# GCtoUSBv1_1.net
KiCad netlist of a schematic drawn in EAGLE
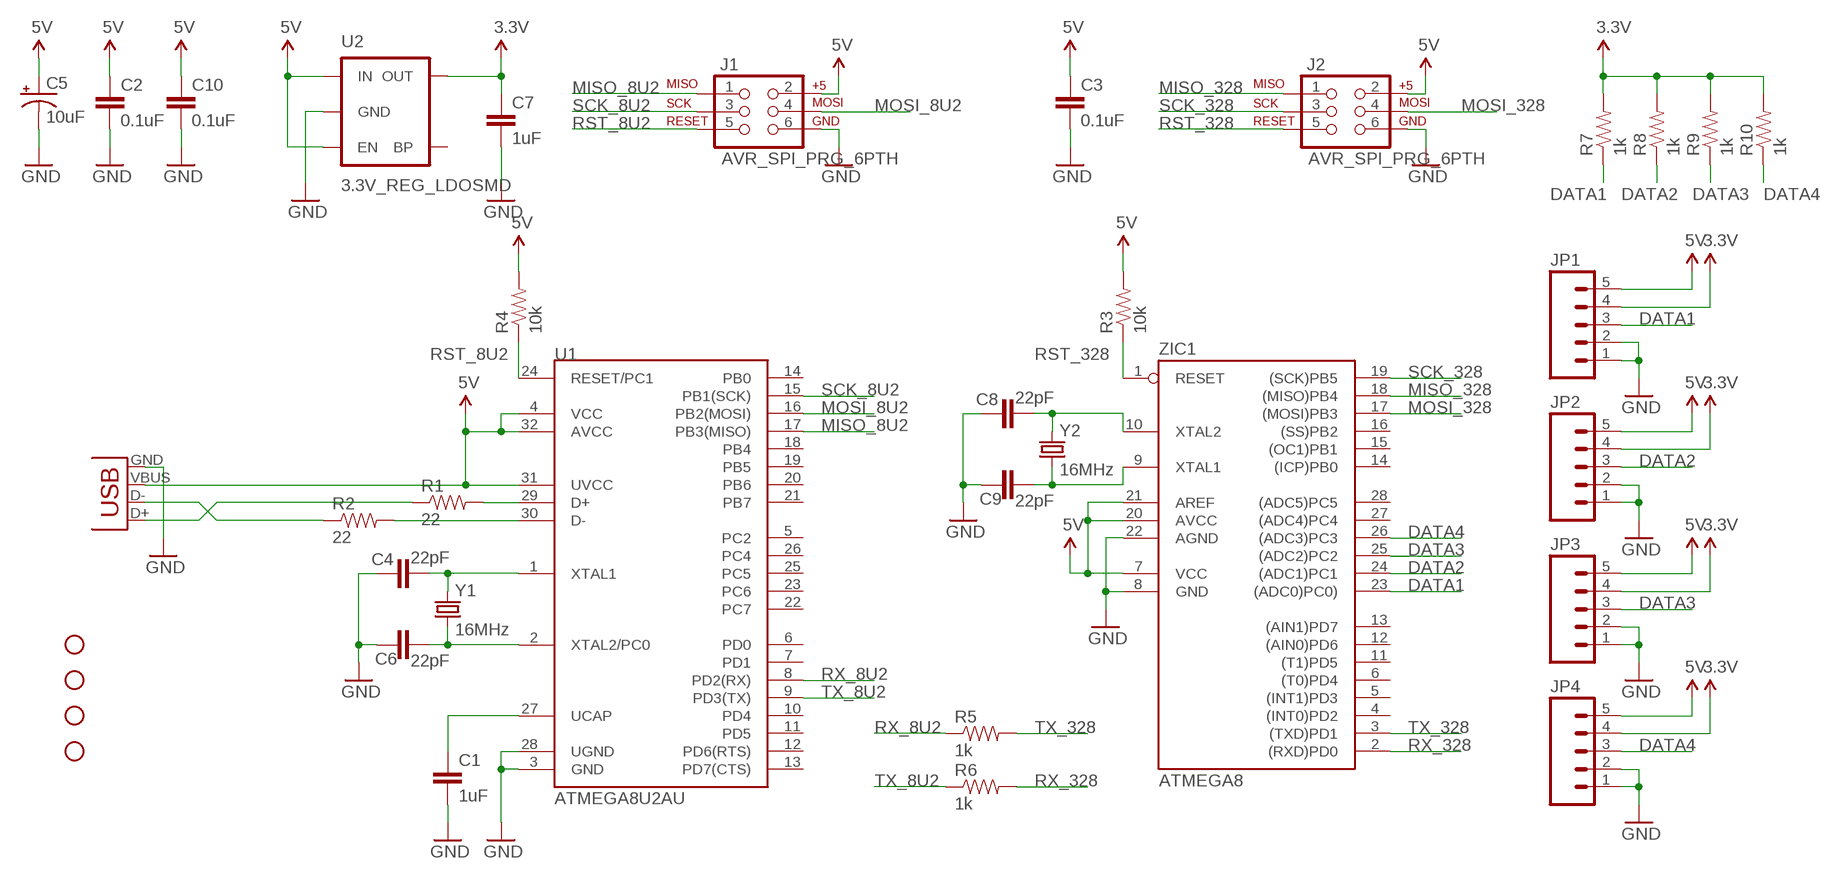
[diagram p0: schematic, sheet 1]

(export (version "E")
  (design (tool "Eeschema 10.0.6"))
  (components
    (comp (ref "C1")
      (value "1uF")
      (footprint "eagle-import:CAP-PTH-5MM")
      (libsource (lib "eagle-import") (part "CAPPTH1"))
    )
    (comp (ref "C2")
      (value "0.1uF")
      (footprint "eagle-import:CAP-PTH-SMALL")
      (libsource (lib "eagle-import") (part "CAPPTH"))
    )
    (comp (ref "C3")
      (value "0.1uF")
      (footprint "eagle-import:CAP-PTH-SMALL")
      (libsource (lib "eagle-import") (part "CAPPTH"))
    )
    (comp (ref "C4")
      (value "22pF")
      (footprint "eagle-import:CAP-PTH-SMALL")
      (libsource (lib "eagle-import") (part "CAPPTH"))
    )
    (comp (ref "C5")
      (value "10uF")
      (footprint "eagle-import:CPOL-RADIAL-10UF-25V")
      (libsource (lib "eagle-import") (part "CAP_POLPTH2"))
    )
    (comp (ref "C6")
      (value "22pF")
      (footprint "eagle-import:CAP-PTH-SMALL")
      (libsource (lib "eagle-import") (part "CAPPTH"))
    )
    (comp (ref "C7")
      (value "1uF")
      (footprint "eagle-import:CAP-PTH-5MM")
      (libsource (lib "eagle-import") (part "CAPPTH1"))
    )
    (comp (ref "C8")
      (value "22pF")
      (footprint "eagle-import:CAP-PTH-SMALL")
      (libsource (lib "eagle-import") (part "CAPPTH"))
    )
    (comp (ref "C9")
      (value "22pF")
      (footprint "eagle-import:CAP-PTH-SMALL")
      (libsource (lib "eagle-import") (part "CAPPTH"))
    )
    (comp (ref "C10")
      (value "0.1uF")
      (footprint "eagle-import:CAP-PTH-SMALL")
      (libsource (lib "eagle-import") (part "CAPPTH"))
    )
    (comp (ref "J1")
      (value "AVR_SPI_PRG_6PTH")
      (footprint "eagle-import:2X3")
      (libsource (lib "eagle-import") (part "AVR_SPI_PRG_6PTH"))
    )
    (comp (ref "J2")
      (value "AVR_SPI_PRG_6PTH")
      (footprint "eagle-import:2X3")
      (libsource (lib "eagle-import") (part "AVR_SPI_PRG_6PTH"))
    )
    (comp (ref "JP1")
      (value "M05PTH")
      (footprint "eagle-import:1X05")
      (libsource (lib "eagle-import") (part "M05PTH"))
    )
    (comp (ref "JP2")
      (value "M05PTH")
      (footprint "eagle-import:1X05")
      (libsource (lib "eagle-import") (part "M05PTH"))
    )
    (comp (ref "JP3")
      (value "M05PTH")
      (footprint "eagle-import:1X05")
      (libsource (lib "eagle-import") (part "M05PTH"))
    )
    (comp (ref "JP4")
      (value "M05PTH")
      (footprint "eagle-import:1X05")
      (libsource (lib "eagle-import") (part "M05PTH"))
    )
    (comp (ref "JP5")
      (value "STAND-OFF")
      (footprint "eagle-import:STAND-OFF")
      (libsource (lib "eagle-import") (part "STAND-OFF"))
    )
    (comp (ref "JP6")
      (value "STAND-OFF")
      (footprint "eagle-import:STAND-OFF")
      (libsource (lib "eagle-import") (part "STAND-OFF"))
    )
    (comp (ref "JP7")
      (value "STAND-OFF")
      (footprint "eagle-import:STAND-OFF")
      (libsource (lib "eagle-import") (part "STAND-OFF"))
    )
    (comp (ref "JP8")
      (value "STAND-OFF")
      (footprint "eagle-import:STAND-OFF")
      (libsource (lib "eagle-import") (part "STAND-OFF"))
    )
    (comp (ref "R1")
      (value "22")
      (footprint "eagle-import:AXIAL-0.4")
      (libsource (lib "eagle-import") (part "RESISTORPTH-1/4W"))
    )
    (comp (ref "R2")
      (value "22")
      (footprint "eagle-import:AXIAL-0.4")
      (libsource (lib "eagle-import") (part "RESISTORPTH-1/4W"))
    )
    (comp (ref "R3")
      (value "10k")
      (footprint "eagle-import:AXIAL-0.5")
      (libsource (lib "eagle-import") (part "RESISTORPTH-1/2W"))
    )
    (comp (ref "R4")
      (value "10k")
      (footprint "eagle-import:AXIAL-0.5")
      (libsource (lib "eagle-import") (part "RESISTORPTH-1/2W"))
    )
    (comp (ref "R5")
      (value "1k")
      (footprint "eagle-import:AXIAL-0.5")
      (libsource (lib "eagle-import") (part "RESISTORPTH-1/2W"))
    )
    (comp (ref "R6")
      (value "1k")
      (footprint "eagle-import:AXIAL-0.5")
      (libsource (lib "eagle-import") (part "RESISTORPTH-1/2W"))
    )
    (comp (ref "R7")
      (value "1k")
      (footprint "eagle-import:AXIAL-0.5")
      (libsource (lib "eagle-import") (part "RESISTORPTH-1/2W"))
    )
    (comp (ref "R8")
      (value "1k")
      (footprint "eagle-import:AXIAL-0.5")
      (libsource (lib "eagle-import") (part "RESISTORPTH-1/2W"))
    )
    (comp (ref "R9")
      (value "1k")
      (footprint "eagle-import:AXIAL-0.5")
      (libsource (lib "eagle-import") (part "RESISTORPTH-1/2W"))
    )
    (comp (ref "R10")
      (value "1k")
      (footprint "eagle-import:AXIAL-0.5")
      (libsource (lib "eagle-import") (part "RESISTORPTH-1/2W"))
    )
    (comp (ref "U1")
      (value "ATMEGA8U2AU")
      (footprint "eagle-import:TQFP32-08")
      (libsource (lib "eagle-import") (part "ATMEGA8U2AU"))
    )
    (comp (ref "U2")
      (value "3.3V_REG_LDOSMD")
      (footprint "eagle-import:SOT23-5")
      (libsource (lib "eagle-import") (part "V_REG_LDOSMD"))
    )
    (comp (ref "X1")
      (value "USBSMD")
      (footprint "eagle-import:USB-MINIB")
      (libsource (lib "eagle-import") (part "USBSMD"))
    )
    (comp (ref "Y1")
      (value "16MHz")
      (footprint "eagle-import:HC49US")
      (libsource (lib "eagle-import") (part "CRYSTALHC49US"))
    )
    (comp (ref "Y2")
      (value "16MHz")
      (footprint "eagle-import:HC49US")
      (libsource (lib "eagle-import") (part "CRYSTALHC49US"))
    )
    (comp (ref "ZIC1")
      (value "ATMEGA8")
      (footprint "eagle-import:DIL28-3")
      (libsource (lib "eagle-import") (part "AT90S4433P"))
    )
  )
  (nets
    (net (code "1") (name "/DATA1") (class "Default")
      (node (ref "JP1") (pin "3") (pinfunction "3_3") (pintype "passive"))
      (node (ref "R7") (pin "P$1") (pinfunction "1_P$1") (pintype "passive"))
      (node (ref "ZIC1") (pin "23") (pinfunction "(ADC0)PC0)_23") (pintype "bidirectional"))
    )
    (net (code "2") (name "/DATA2") (class "Default")
      (node (ref "JP2") (pin "3") (pinfunction "3_3") (pintype "passive"))
      (node (ref "R8") (pin "P$1") (pinfunction "1_P$1") (pintype "passive"))
      (node (ref "ZIC1") (pin "24") (pinfunction "(ADC1)PC1_24") (pintype "bidirectional"))
    )
    (net (code "3") (name "/DATA3") (class "Default")
      (node (ref "JP3") (pin "3") (pinfunction "3_3") (pintype "passive"))
      (node (ref "R9") (pin "P$1") (pinfunction "1_P$1") (pintype "passive"))
      (node (ref "ZIC1") (pin "25") (pinfunction "(ADC2)PC2_25") (pintype "bidirectional"))
    )
    (net (code "4") (name "/DATA4") (class "Default")
      (node (ref "JP4") (pin "3") (pinfunction "3_3") (pintype "passive"))
      (node (ref "R10") (pin "P$1") (pinfunction "1_P$1") (pintype "passive"))
      (node (ref "ZIC1") (pin "26") (pinfunction "(ADC3)PC3_26") (pintype "bidirectional"))
    )
    (net (code "5") (name "/MISO_8U2") (class "Default")
      (node (ref "J1") (pin "1") (pinfunction "1_1") (pintype "passive"))
      (node (ref "U1") (pin "17") (pinfunction "PB3(MISO)_17") (pintype "bidirectional"))
    )
    (net (code "6") (name "/MISO_328") (class "Default")
      (node (ref "J2") (pin "1") (pinfunction "1_1") (pintype "passive"))
      (node (ref "ZIC1") (pin "18") (pinfunction "(MISO)PB4_18") (pintype "bidirectional"))
    )
    (net (code "7") (name "/MOSI_8U2") (class "Default")
      (node (ref "J1") (pin "4") (pinfunction "4_4") (pintype "passive"))
      (node (ref "U1") (pin "16") (pinfunction "PB2(MOSI)_16") (pintype "bidirectional"))
    )
    (net (code "8") (name "/MOSI_328") (class "Default")
      (node (ref "J2") (pin "4") (pinfunction "4_4") (pintype "passive"))
      (node (ref "ZIC1") (pin "17") (pinfunction "(MOSI)PB3_17") (pintype "bidirectional"))
    )
    (net (code "9") (name "/RST_8U2") (class "Default")
      (node (ref "J1") (pin "5") (pinfunction "5_5") (pintype "passive"))
      (node (ref "R4") (pin "P$1") (pinfunction "1_P$1") (pintype "passive"))
      (node (ref "U1") (pin "24") (pinfunction "RESET/PC1_24") (pintype "bidirectional"))
    )
    (net (code "10") (name "/RST_328") (class "Default")
      (node (ref "J2") (pin "5") (pinfunction "5_5") (pintype "passive"))
      (node (ref "R3") (pin "P$1") (pinfunction "1_P$1") (pintype "passive"))
      (node (ref "ZIC1") (pin "1") (pinfunction "RESET_1") (pintype "input"))
    )
    (net (code "11") (name "/RX_8U2") (class "Default")
      (node (ref "R5") (pin "P$1") (pinfunction "1_P$1") (pintype "passive"))
      (node (ref "U1") (pin "8") (pinfunction "PD2(RX)_8") (pintype "bidirectional"))
    )
    (net (code "12") (name "/RX_328") (class "Default")
      (node (ref "R6") (pin "P$2") (pinfunction "2_P$2") (pintype "passive"))
      (node (ref "ZIC1") (pin "2") (pinfunction "(RXD)PD0_2") (pintype "bidirectional"))
    )
    (net (code "13") (name "/SCK_8U2") (class "Default")
      (node (ref "J1") (pin "3") (pinfunction "3_3") (pintype "passive"))
      (node (ref "U1") (pin "15") (pinfunction "PB1(SCK)_15") (pintype "bidirectional"))
    )
    (net (code "14") (name "/SCK_328") (class "Default")
      (node (ref "J2") (pin "3") (pinfunction "3_3") (pintype "passive"))
      (node (ref "ZIC1") (pin "19") (pinfunction "(SCK)PB5_19") (pintype "bidirectional"))
    )
    (net (code "15") (name "/TX_8U2") (class "Default")
      (node (ref "R6") (pin "P$1") (pinfunction "1_P$1") (pintype "passive"))
      (node (ref "U1") (pin "9") (pinfunction "PD3(TX)_9") (pintype "bidirectional"))
    )
    (net (code "16") (name "/TX_328") (class "Default")
      (node (ref "R5") (pin "P$2") (pinfunction "2_P$2") (pintype "passive"))
      (node (ref "ZIC1") (pin "3") (pinfunction "(TXD)PD1_3") (pintype "bidirectional"))
    )
    (net (code "17") (name "3.3V") (class "Default")
      (node (ref "C7") (pin "1") (pinfunction "1_1") (pintype "passive"))
      (node (ref "JP1") (pin "4") (pinfunction "4_4") (pintype "passive"))
      (node (ref "JP2") (pin "4") (pinfunction "4_4") (pintype "passive"))
      (node (ref "JP3") (pin "4") (pinfunction "4_4") (pintype "passive"))
      (node (ref "JP4") (pin "4") (pinfunction "4_4") (pintype "passive"))
      (node (ref "R10") (pin "P$2") (pinfunction "2_P$2") (pintype "passive"))
      (node (ref "R7") (pin "P$2") (pinfunction "2_P$2") (pintype "passive"))
      (node (ref "R8") (pin "P$2") (pinfunction "2_P$2") (pintype "passive"))
      (node (ref "R9") (pin "P$2") (pinfunction "2_P$2") (pintype "passive"))
      (node (ref "U2") (pin "5") (pinfunction "OUT_5") (pintype "passive"))
    )
    (net (code "18") (name "5V") (class "Default")
      (node (ref "C10") (pin "1") (pinfunction "1_1") (pintype "passive"))
      (node (ref "C2") (pin "1") (pinfunction "1_1") (pintype "passive"))
      (node (ref "C3") (pin "1") (pinfunction "1_1") (pintype "passive"))
      (node (ref "C5") (pin "1") (pinfunction "+_1") (pintype "passive"))
      (node (ref "J1") (pin "2") (pinfunction "2_2") (pintype "passive"))
      (node (ref "J2") (pin "2") (pinfunction "2_2") (pintype "passive"))
      (node (ref "JP1") (pin "5") (pinfunction "5_5") (pintype "passive"))
      (node (ref "JP2") (pin "5") (pinfunction "5_5") (pintype "passive"))
      (node (ref "JP3") (pin "5") (pinfunction "5_5") (pintype "passive"))
      (node (ref "JP4") (pin "5") (pinfunction "5_5") (pintype "passive"))
      (node (ref "R3") (pin "P$2") (pinfunction "2_P$2") (pintype "passive"))
      (node (ref "R4") (pin "P$2") (pinfunction "2_P$2") (pintype "passive"))
      (node (ref "U1") (pin "31") (pinfunction "UVCC_31") (pintype "bidirectional"))
      (node (ref "U1") (pin "32") (pinfunction "AVCC_32") (pintype "bidirectional"))
      (node (ref "U1") (pin "4") (pinfunction "VCC_4") (pintype "bidirectional"))
      (node (ref "U2") (pin "1") (pinfunction "IN_1") (pintype "input"))
      (node (ref "U2") (pin "3") (pinfunction "EN_3") (pintype "input"))
      (node (ref "X1") (pin "VBUS") (pinfunction "VBUS_VBUS") (pintype "bidirectional"))
      (node (ref "ZIC1") (pin "20") (pinfunction "AVCC_20") (pintype "power_in"))
      (node (ref "ZIC1") (pin "21") (pinfunction "AREF_21") (pintype "passive"))
      (node (ref "ZIC1") (pin "7") (pinfunction "VCC_7") (pintype "power_in"))
    )
    (net (code "19") (name "GND") (class "Default")
      (node (ref "C1") (pin "2") (pinfunction "2_2") (pintype "passive"))
      (node (ref "C10") (pin "2") (pinfunction "2_2") (pintype "passive"))
      (node (ref "C2") (pin "2") (pinfunction "2_2") (pintype "passive"))
      (node (ref "C3") (pin "2") (pinfunction "2_2") (pintype "passive"))
      (node (ref "C4") (pin "2") (pinfunction "2_2") (pintype "passive"))
      (node (ref "C5") (pin "2") (pinfunction "-_2") (pintype "passive"))
      (node (ref "C6") (pin "2") (pinfunction "2_2") (pintype "passive"))
      (node (ref "C7") (pin "2") (pinfunction "2_2") (pintype "passive"))
      (node (ref "C8") (pin "2") (pinfunction "2_2") (pintype "passive"))
      (node (ref "C9") (pin "2") (pinfunction "2_2") (pintype "passive"))
      (node (ref "J1") (pin "6") (pinfunction "6_6") (pintype "passive"))
      (node (ref "J2") (pin "6") (pinfunction "6_6") (pintype "passive"))
      (node (ref "JP1") (pin "1") (pinfunction "1_1") (pintype "passive"))
      (node (ref "JP1") (pin "2") (pinfunction "2_2") (pintype "passive"))
      (node (ref "JP2") (pin "1") (pinfunction "1_1") (pintype "passive"))
      (node (ref "JP2") (pin "2") (pinfunction "2_2") (pintype "passive"))
      (node (ref "JP3") (pin "1") (pinfunction "1_1") (pintype "passive"))
      (node (ref "JP3") (pin "2") (pinfunction "2_2") (pintype "passive"))
      (node (ref "JP4") (pin "1") (pinfunction "1_1") (pintype "passive"))
      (node (ref "JP4") (pin "2") (pinfunction "2_2") (pintype "passive"))
      (node (ref "U1") (pin "28") (pinfunction "UGND_28") (pintype "bidirectional"))
      (node (ref "U1") (pin "3") (pinfunction "GND_3") (pintype "bidirectional"))
      (node (ref "U2") (pin "2") (pinfunction "GND_2") (pintype "input"))
      (node (ref "X1") (pin "GND") (pinfunction "GND_GND") (pintype "bidirectional"))
      (node (ref "ZIC1") (pin "22") (pinfunction "AGND_22") (pintype "power_in"))
      (node (ref "ZIC1") (pin "8") (pinfunction "GND_8") (pintype "power_in"))
    )
    (net (code "20") (name "Net-(R1-1)") (class "Default")
      (node (ref "R1") (pin "P$1") (pinfunction "1_P$1") (pintype "passive"))
      (node (ref "X1") (pin "D+") (pinfunction "D+_D+") (pintype "bidirectional"))
    )
    (net (code "21") (name "Net-(R1-2)") (class "Default")
      (node (ref "R1") (pin "P$2") (pinfunction "2_P$2") (pintype "passive"))
      (node (ref "U1") (pin "29") (pinfunction "D+_29") (pintype "bidirectional"))
    )
    (net (code "22") (name "Net-(R2-1)") (class "Default")
      (node (ref "R2") (pin "P$1") (pinfunction "1_P$1") (pintype "passive"))
      (node (ref "X1") (pin "D-") (pinfunction "D-_D-") (pintype "bidirectional"))
    )
    (net (code "23") (name "Net-(R2-2)") (class "Default")
      (node (ref "R2") (pin "P$2") (pinfunction "2_P$2") (pintype "passive"))
      (node (ref "U1") (pin "30") (pinfunction "D-_30") (pintype "bidirectional"))
    )
    (net (code "24") (name "Net-(U1-UCAP)") (class "Default")
      (node (ref "C1") (pin "1") (pinfunction "1_1") (pintype "passive"))
      (node (ref "U1") (pin "27") (pinfunction "UCAP_27") (pintype "bidirectional"))
    )
    (net (code "25") (name "Net-(U1-XTAL1)") (class "Default")
      (node (ref "C4") (pin "1") (pinfunction "1_1") (pintype "passive"))
      (node (ref "U1") (pin "1") (pinfunction "XTAL1_1") (pintype "bidirectional"))
      (node (ref "Y1") (pin "2") (pinfunction "2_2") (pintype "passive"))
    )
    (net (code "26") (name "Net-(U1-XTAL2{slash}PC0)") (class "Default")
      (node (ref "C6") (pin "1") (pinfunction "1_1") (pintype "passive"))
      (node (ref "U1") (pin "2") (pinfunction "XTAL2/PC0_2") (pintype "bidirectional"))
      (node (ref "Y1") (pin "1") (pinfunction "1_1") (pintype "passive"))
    )
    (net (code "27") (name "Net-(ZIC1-XTAL1)") (class "Default")
      (node (ref "C9") (pin "1") (pinfunction "1_1") (pintype "passive"))
      (node (ref "Y2") (pin "1") (pinfunction "1_1") (pintype "passive"))
      (node (ref "ZIC1") (pin "9") (pinfunction "XTAL1_9") (pintype "bidirectional"))
    )
    (net (code "28") (name "Net-(ZIC1-XTAL2)") (class "Default")
      (node (ref "C8") (pin "1") (pinfunction "1_1") (pintype "passive"))
      (node (ref "Y2") (pin "2") (pinfunction "2_2") (pintype "passive"))
      (node (ref "ZIC1") (pin "10") (pinfunction "XTAL2_10") (pintype "bidirectional"))
    )
    (net (code "29") (name "unconnected-(U1-PB0-Pad14)") (class "Default")
      (node (ref "U1") (pin "14") (pinfunction "PB0_14") (pintype "bidirectional"))
    )
    (net (code "30") (name "unconnected-(U1-PB4-Pad18)") (class "Default")
      (node (ref "U1") (pin "18") (pinfunction "PB4_18") (pintype "bidirectional"))
    )
    (net (code "31") (name "unconnected-(U1-PB5-Pad19)") (class "Default")
      (node (ref "U1") (pin "19") (pinfunction "PB5_19") (pintype "bidirectional"))
    )
    (net (code "32") (name "unconnected-(U1-PB6-Pad20)") (class "Default")
      (node (ref "U1") (pin "20") (pinfunction "PB6_20") (pintype "bidirectional"))
    )
    (net (code "33") (name "unconnected-(U1-PB7-Pad21)") (class "Default")
      (node (ref "U1") (pin "21") (pinfunction "PB7_21") (pintype "bidirectional"))
    )
    (net (code "34") (name "unconnected-(U1-PC2-Pad5)") (class "Default")
      (node (ref "U1") (pin "5") (pinfunction "PC2_5") (pintype "bidirectional"))
    )
    (net (code "35") (name "unconnected-(U1-PC4-Pad26)") (class "Default")
      (node (ref "U1") (pin "26") (pinfunction "PC4_26") (pintype "bidirectional"))
    )
    (net (code "36") (name "unconnected-(U1-PC5-Pad25)") (class "Default")
      (node (ref "U1") (pin "25") (pinfunction "PC5_25") (pintype "bidirectional"))
    )
    (net (code "37") (name "unconnected-(U1-PC6-Pad23)") (class "Default")
      (node (ref "U1") (pin "23") (pinfunction "PC6_23") (pintype "bidirectional"))
    )
    (net (code "38") (name "unconnected-(U1-PC7-Pad22)") (class "Default")
      (node (ref "U1") (pin "22") (pinfunction "PC7_22") (pintype "bidirectional"))
    )
    (net (code "39") (name "unconnected-(U1-PD0-Pad6)") (class "Default")
      (node (ref "U1") (pin "6") (pinfunction "PD0_6") (pintype "bidirectional"))
    )
    (net (code "40") (name "unconnected-(U1-PD1-Pad7)") (class "Default")
      (node (ref "U1") (pin "7") (pinfunction "PD1_7") (pintype "bidirectional"))
    )
    (net (code "41") (name "unconnected-(U1-PD4-Pad10)") (class "Default")
      (node (ref "U1") (pin "10") (pinfunction "PD4_10") (pintype "bidirectional"))
    )
    (net (code "42") (name "unconnected-(U1-PD5-Pad11)") (class "Default")
      (node (ref "U1") (pin "11") (pinfunction "PD5_11") (pintype "bidirectional"))
    )
    (net (code "43") (name "unconnected-(U1-PD6(RTS)-Pad12)") (class "Default")
      (node (ref "U1") (pin "12") (pinfunction "PD6(RTS)_12") (pintype "bidirectional"))
    )
    (net (code "44") (name "unconnected-(U1-PD7(CTS)-Pad13)") (class "Default")
      (node (ref "U1") (pin "13") (pinfunction "PD7(CTS)_13") (pintype "bidirectional"))
    )
    (net (code "45") (name "unconnected-(U2-BP-Pad4)") (class "Default")
      (node (ref "U2") (pin "4") (pinfunction "BP_4") (pintype "input"))
    )
    (net (code "46") (name "unconnected-(ZIC1-(ADC4)PC4-Pad27)") (class "Default")
      (node (ref "ZIC1") (pin "27") (pinfunction "(ADC4)PC4_27") (pintype "bidirectional"))
    )
    (net (code "47") (name "unconnected-(ZIC1-(ADC5)PC5-Pad28)") (class "Default")
      (node (ref "ZIC1") (pin "28") (pinfunction "(ADC5)PC5_28") (pintype "bidirectional"))
    )
    (net (code "48") (name "unconnected-(ZIC1-(AIN0)PD6-Pad12)") (class "Default")
      (node (ref "ZIC1") (pin "12") (pinfunction "(AIN0)PD6_12") (pintype "bidirectional"))
    )
    (net (code "49") (name "unconnected-(ZIC1-(AIN1)PD7-Pad13)") (class "Default")
      (node (ref "ZIC1") (pin "13") (pinfunction "(AIN1)PD7_13") (pintype "bidirectional"))
    )
    (net (code "50") (name "unconnected-(ZIC1-(ICP)PB0-Pad14)") (class "Default")
      (node (ref "ZIC1") (pin "14") (pinfunction "(ICP)PB0_14") (pintype "bidirectional"))
    )
    (net (code "51") (name "unconnected-(ZIC1-(INT0)PD2-Pad4)") (class "Default")
      (node (ref "ZIC1") (pin "4") (pinfunction "(INT0)PD2_4") (pintype "bidirectional"))
    )
    (net (code "52") (name "unconnected-(ZIC1-(INT1)PD3-Pad5)") (class "Default")
      (node (ref "ZIC1") (pin "5") (pinfunction "(INT1)PD3_5") (pintype "bidirectional"))
    )
    (net (code "53") (name "unconnected-(ZIC1-(OC1)PB1-Pad15)") (class "Default")
      (node (ref "ZIC1") (pin "15") (pinfunction "(OC1)PB1_15") (pintype "bidirectional"))
    )
    (net (code "54") (name "unconnected-(ZIC1-(SS)PB2-Pad16)") (class "Default")
      (node (ref "ZIC1") (pin "16") (pinfunction "(SS)PB2_16") (pintype "bidirectional"))
    )
    (net (code "55") (name "unconnected-(ZIC1-(T0)PD4-Pad6)") (class "Default")
      (node (ref "ZIC1") (pin "6") (pinfunction "(T0)PD4_6") (pintype "bidirectional"))
    )
    (net (code "56") (name "unconnected-(ZIC1-(T1)PD5-Pad11)") (class "Default")
      (node (ref "ZIC1") (pin "11") (pinfunction "(T1)PD5_11") (pintype "bidirectional"))
    )
  )
)
